# PowerConversion.net
KiCad netlist of a schematic drawn in Altium Designer
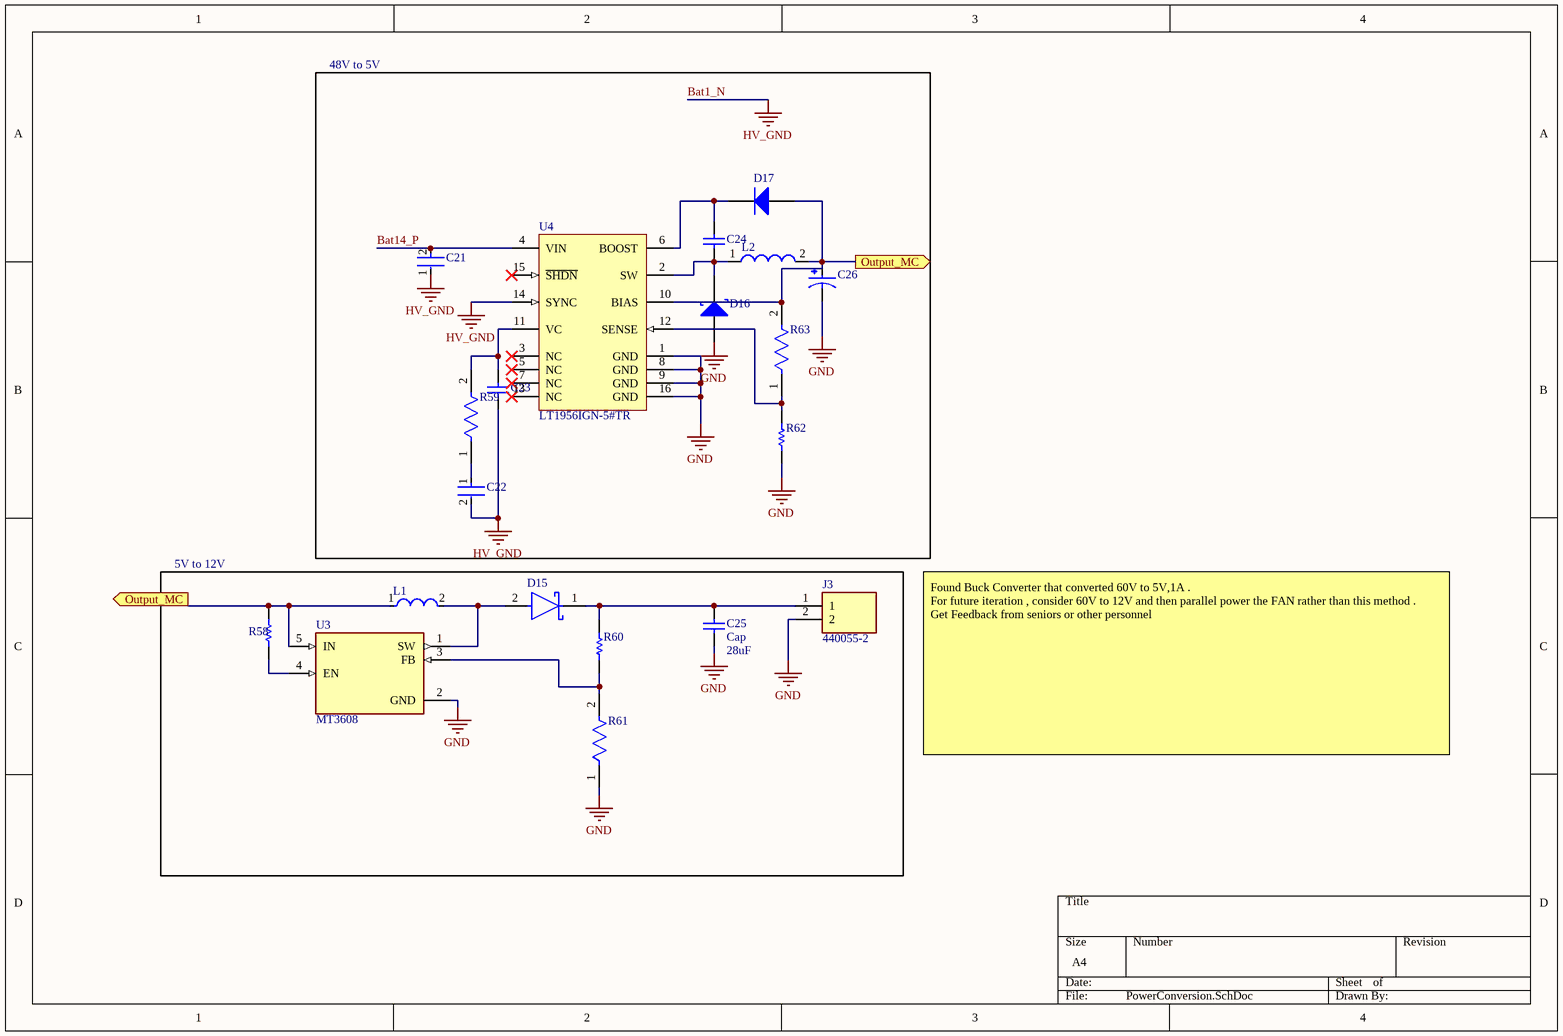
[diagram p0: PowerConversion.SchDoc]

(export (version "E")
  (design (tool "Eeschema 10.0.6"))
  (components
    (comp (ref "C21")
      (value "18121C225KAZ2A")
      (footprint "FP-1812-L_4_5_0_3-W_3_2_0-IPC_C")
      (description "General Purpose Ceramic Capacitor, 1812, 2.2uF, 10%, X7R, 15%, 100V")
      (fields (field (name "TOLERANCE") "10%") (field (name "VOLTAGE") "100V"))
      (libsource (lib "Altium Content Vault") (part "6d4d395cd7362dd47ce0157d173177e"))
    )
    (comp (ref "C22")
      (value "CC0603KRX7R9BB223")
      (footprint "FP-CC0603-DA-MFG")
      (description "CAP CER 0.022UF 50V X7R 0603")
      (fields (field (name "TOLERANCE") "10%") (field (name "VOLTAGE") "50V"))
      (libsource (lib "Altium Content Vault") (part "11868f565c42a9108669ba33697ecf6"))
    )
    (comp (ref "C23")
      (value "C0805C221K5RACTU")
      (footprint "CAPC2013X88X50LL20T25")
      (fields (field (name "MANUFACTURER") "Kemet"))
      (libsource (lib "Altium Content Vault") (part "CAP"))
    )
    (comp (ref "C24")
      (value "04025A331JAT2A")
      (footprint "CAPC1005X56X25NL10T15")
      (fields (field (name "MANUFACTURER") "AVX Interconnect / Elco"))
      (libsource (lib "Altium Content Vault") (part "CAP"))
    )
    (comp (ref "C25")
      (value "Cap")
      (footprint "RAD-0.3")
      (description "Capacitor")
      (fields (field (name "ALTIUM_VALUE") "28uF") (field (name "PUBLISHER") "Altium Limited"))
      (libsource (lib "Miscellaneous Devices") (part "Cap"))
    )
    (comp (ref "C26")
      (value "EEE1AA101WR")
      (footprint "CAP_EEE1AA101WR")
      (fields (field (name "MF") "{'manufacturer': u'Panasonic'}"))
      (libsource (lib "SnapEDA_Library") (part "EEE1AA101WR"))
    )
    (comp (ref "D15")
      (value "SS34-E3/57T")
      (footprint "FP-95402-MFG")
      (description "DIODE SCHOTTKY 40V 3A DO214AB")
      (fields
        (field (name "MANUFACTURER") "Vishay")
        (field (name "OCTOPART") "https://octopart.com/ss34-e3%2F57t-vishay-39552907")
      )
      (libsource (lib "Altium Content Vault") (part "1d6ec82d83fb6aee721767c19dac4b9"))
    )
    (comp (ref "D16")
      (value "VS-10MQ060NTRPBF")
      (footprint "VISH-DO-214AC_V")
      (fields (field (name "MANUFACTURER") "Vishay"))
      (libsource (lib "Altium Content Vault") (part "DSKY-AK-2"))
    )
    (comp (ref "D17")
      (value "1N4148W-7-F")
      (footprint "DIOD-SOD123-2_V")
      (description "Fast Switching Diode, 100 V, 0.15 A, -65 to 150 degC, 2-Pin?SOD123, RoHS, Tape and Reel")
      (fields (field (name "MANUFACTURER") "DiodesIncorporated"))
      (libsource (lib "Altium Content Vault") (part "D-AK-2"))
    )
    (comp (ref "J3")
      (value "440055-2")
      (footprint "TE_440055-2")
      (fields (field (name "MF") "{'manufacturer': u'TE Connectivity'}"))
      (libsource (lib "SnapEDA_Library") (part "440055-2"))
    )
    (comp (ref "L1")
      (value "IHLP2525CZER220M11")
      (footprint "FP-IHLP-2525CZ-FP_2_413x3-MFG")
      (description "Commercial Inductors, Low DCR Series 22uH 2.9A 135mΩ 20%")
      (fields (field (name "TOLERANCE") "20%"))
      (libsource (lib "Altium Content Vault") (part "725321dda6339637d4d059423bc1c3c"))
    )
    (comp (ref "L2")
      (value "7447471473")
      (footprint "WE-TIS 1111")
      (description "Shielded Radial Leaded Wire Wound Inductor WE-TIS, L=47000 µH")
      (fields (field (name "MANUFACTURER") "Wuerth Elektronik"))
      (libsource (lib "Altium Content Vault") (part "PAS-IND-INDUCTOR-2"))
    )
    (comp (ref "R58")
      (value "CRCW040210K0FKEDHP")
      (footprint "RESC1005X40X25ML05T10")
      (fields (field (name "MANUFACTURER") "Vishay Dale"))
      (libsource (lib "Altium Content Vault") (part "RES"))
    )
    (comp (ref "R59")
      (value "AC0402FR-072K2L")
      (footprint "FP-AC0402-IPC_A")
      (description "RES 2.2kΩ ±1% 0.063W 0402")
      (fields (field (name "TOLERANCE") "1%"))
      (libsource (lib "Altium Content Vault") (part "1029c3af85768c4190bb7ad29bc67b5"))
    )
    (comp (ref "R60")
      (value "CRCW040262K0FKED")
      (footprint "RESC1005X40X25LL05T05")
      (fields (field (name "MANUFACTURER") "Vishay Dale"))
      (libsource (lib "Altium Content Vault") (part "RES"))
    )
    (comp (ref "R61")
      (value "AC0402FR-073K3L")
      (footprint "FP-AC0402-IPC_B")
      (description "RES 3.3kΩ ±1% 0.063W 0402")
      (fields (field (name "TOLERANCE") "1%"))
      (libsource (lib "Altium Content Vault") (part "1029c3af85768c4190bb7ad29bc67b5"))
    )
    (comp (ref "R62")
      (value "ERA6AEB4991V")
      (footprint "RESC2013X60X40ML20T25")
      (fields (field (name "MANUFACTURER") "Panasonic"))
      (libsource (lib "Altium Content Vault") (part "RES"))
    )
    (comp (ref "R63")
      (value "RG2012N-1542-D-T5")
      (footprint "FP-RG2012-IPC_C")
      (description "Automotive Metal Thin Film Chip Resistor, 0805, 15.4kΩ, 0.5%, 10ppm/°C, 0.125W, 150V")
      (fields (field (name "TOLERANCE") "0.5%"))
      (libsource (lib "Altium Content Vault") (part "1029c3af85768c4190bb7ad29bc67b5"))
    )
    (comp (ref "U3")
      (value "MT3608")
      (footprint "SOT95P280X145-6N")
      (description "High Efficiency 1.2MHz 2A Step Up Converter")
      (fields (field (name "MF") "{'manufacturer': u'Aerosemi Technology Co., Ltd'}"))
      (libsource (lib "SnapEDA_Library") (part "MT3608"))
    )
    (comp (ref "U4")
      (value "LT1956IGN-5#TR")
      (footprint "LT-GN-16_M")
      (fields (field (name "MANUFACTURER") "Linear Technology"))
      (libsource (lib "Altium Content Vault") (part "LT-LT1766_1956-GN-16"))
    )
  )
  (nets
    (net (code "1") (name "/Bat14_P") (class "Default")
      (node (ref "C21") (pin "2") (pinfunction "2_2") (pintype "passive"))
      (node (ref "U4") (pin "4") (pinfunction "VIN_4") (pintype "power_in"))
    )
    (net (code "2") (name "/Output_MC") (class "Default")
      (node (ref "C26") (pin "1") (pinfunction "1_1") (pintype "passive"))
      (node (ref "D17") (pin "1") (pinfunction "A_1") (pintype "passive"))
      (node (ref "L1") (pin "1") (pinfunction "1_1") (pintype "passive"))
      (node (ref "L2") (pin "2") (pinfunction "2_2") (pintype "passive"))
      (node (ref "R58") (pin "2") (pinfunction "2_2") (pintype "passive"))
      (node (ref "R63") (pin "2") (pinfunction "2_2") (pintype "passive"))
      (node (ref "U3") (pin "5") (pinfunction "IN_5") (pintype "input"))
      (node (ref "U4") (pin "10") (pinfunction "BIAS_10") (pintype "power_in"))
    )
    (net (code "3") (name "GND") (class "Default")
      (node (ref "C25") (pin "1") (pinfunction "1_1") (pintype "passive"))
      (node (ref "C26") (pin "2") (pinfunction "2_2") (pintype "passive"))
      (node (ref "D16") (pin "1") (pinfunction "A_1") (pintype "passive"))
      (node (ref "J3") (pin "2") (pinfunction "2_2") (pintype "passive"))
      (node (ref "R61") (pin "1") (pinfunction "1_1") (pintype "passive"))
      (node (ref "R62") (pin "1") (pinfunction "1_1") (pintype "passive"))
      (node (ref "U3") (pin "2") (pinfunction "GND_2") (pintype "power_in"))
      (node (ref "U4") (pin "1") (pinfunction "GND_1") (pintype "power_in"))
      (node (ref "U4") (pin "16") (pinfunction "GND_16") (pintype "power_in"))
      (node (ref "U4") (pin "8") (pinfunction "GND_8") (pintype "power_in"))
      (node (ref "U4") (pin "9") (pinfunction "GND_9") (pintype "power_in"))
    )
    (net (code "4") (name "HV_GND") (class "Default")
      (node (ref "C21") (pin "1") (pinfunction "1_1") (pintype "passive"))
      (node (ref "C22") (pin "2") (pinfunction "2_2") (pintype "passive"))
      (node (ref "C23") (pin "1") (pinfunction "1_1") (pintype "passive"))
      (node (ref "U4") (pin "14") (pinfunction "SYNC_14") (pintype "input"))
    )
    (net (code "5") (name "Net-(C22-Pad1)") (class "Default")
      (node (ref "C22") (pin "1") (pinfunction "1_1") (pintype "passive"))
      (node (ref "R59") (pin "1") (pinfunction "1_1") (pintype "passive"))
    )
    (net (code "6") (name "Net-(D15-A)") (class "Default")
      (node (ref "D15") (pin "2") (pinfunction "A_2") (pintype "passive"))
      (node (ref "L1") (pin "2") (pinfunction "2_2") (pintype "passive"))
      (node (ref "U3") (pin "1") (pinfunction "SW_1") (pintype "output"))
    )
    (net (code "7") (name "Net-(D15-C)") (class "Default")
      (node (ref "C25") (pin "2") (pinfunction "2_2") (pintype "passive"))
      (node (ref "D15") (pin "1") (pinfunction "C_1") (pintype "passive"))
      (node (ref "J3") (pin "1") (pinfunction "1_1") (pintype "passive"))
      (node (ref "R60") (pin "2") (pinfunction "2_2") (pintype "passive"))
    )
    (net (code "8") (name "Net-(D16-K)") (class "Default")
      (node (ref "C24") (pin "1") (pinfunction "1_1") (pintype "passive"))
      (node (ref "D16") (pin "2") (pinfunction "K_2") (pintype "passive"))
      (node (ref "L2") (pin "1") (pinfunction "1_1") (pintype "passive"))
      (node (ref "U4") (pin "2") (pinfunction "SW_2") (pintype "power_in"))
    )
    (net (code "9") (name "Net-(D17-K)") (class "Default")
      (node (ref "C24") (pin "2") (pinfunction "2_2") (pintype "passive"))
      (node (ref "D17") (pin "2") (pinfunction "K_2") (pintype "passive"))
      (node (ref "U4") (pin "6") (pinfunction "BOOST_6") (pintype "passive"))
    )
    (net (code "10") (name "Net-(U3-EN)") (class "Default")
      (node (ref "R58") (pin "1") (pinfunction "1_1") (pintype "passive"))
      (node (ref "U3") (pin "4") (pinfunction "EN_4") (pintype "input"))
    )
    (net (code "11") (name "Net-(U3-FB)") (class "Default")
      (node (ref "R60") (pin "1") (pinfunction "1_1") (pintype "passive"))
      (node (ref "R61") (pin "2") (pinfunction "2_2") (pintype "passive"))
      (node (ref "U3") (pin "3") (pinfunction "FB_3") (pintype "input"))
    )
    (net (code "12") (name "Net-(U4-SENSE)") (class "Default")
      (node (ref "R62") (pin "2") (pinfunction "2_2") (pintype "passive"))
      (node (ref "R63") (pin "1") (pinfunction "1_1") (pintype "passive"))
      (node (ref "U4") (pin "12") (pinfunction "SENSE_12") (pintype "input"))
    )
    (net (code "13") (name "Net-(U4-VC)") (class "Default")
      (node (ref "C23") (pin "2") (pinfunction "2_2") (pintype "passive"))
      (node (ref "R59") (pin "2") (pinfunction "2_2") (pintype "passive"))
      (node (ref "U4") (pin "11") (pinfunction "VC_11") (pintype "passive"))
    )
    (net (code "14") (name "unconnected-(U4-NC-Pad3)") (class "Default")
      (node (ref "U4") (pin "3") (pinfunction "NC_3") (pintype "passive+no_connect"))
    )
    (net (code "15") (name "unconnected-(U4-NC-Pad5)") (class "Default")
      (node (ref "U4") (pin "5") (pinfunction "NC_5") (pintype "passive+no_connect"))
    )
    (net (code "16") (name "unconnected-(U4-NC-Pad7)") (class "Default")
      (node (ref "U4") (pin "7") (pinfunction "NC_7") (pintype "passive+no_connect"))
    )
    (net (code "17") (name "unconnected-(U4-NC-Pad13)") (class "Default")
      (node (ref "U4") (pin "13") (pinfunction "NC_13") (pintype "passive+no_connect"))
    )
    (net (code "18") (name "unconnected-(U4-~{SHDN}-Pad15)") (class "Default")
      (node (ref "U4") (pin "15") (pinfunction "~{SHDN}_15") (pintype "input+no_connect"))
    )
  )
)
